# Etapa_Control_Ruido.net
KiCad netlist of a schematic drawn in Altium Designer
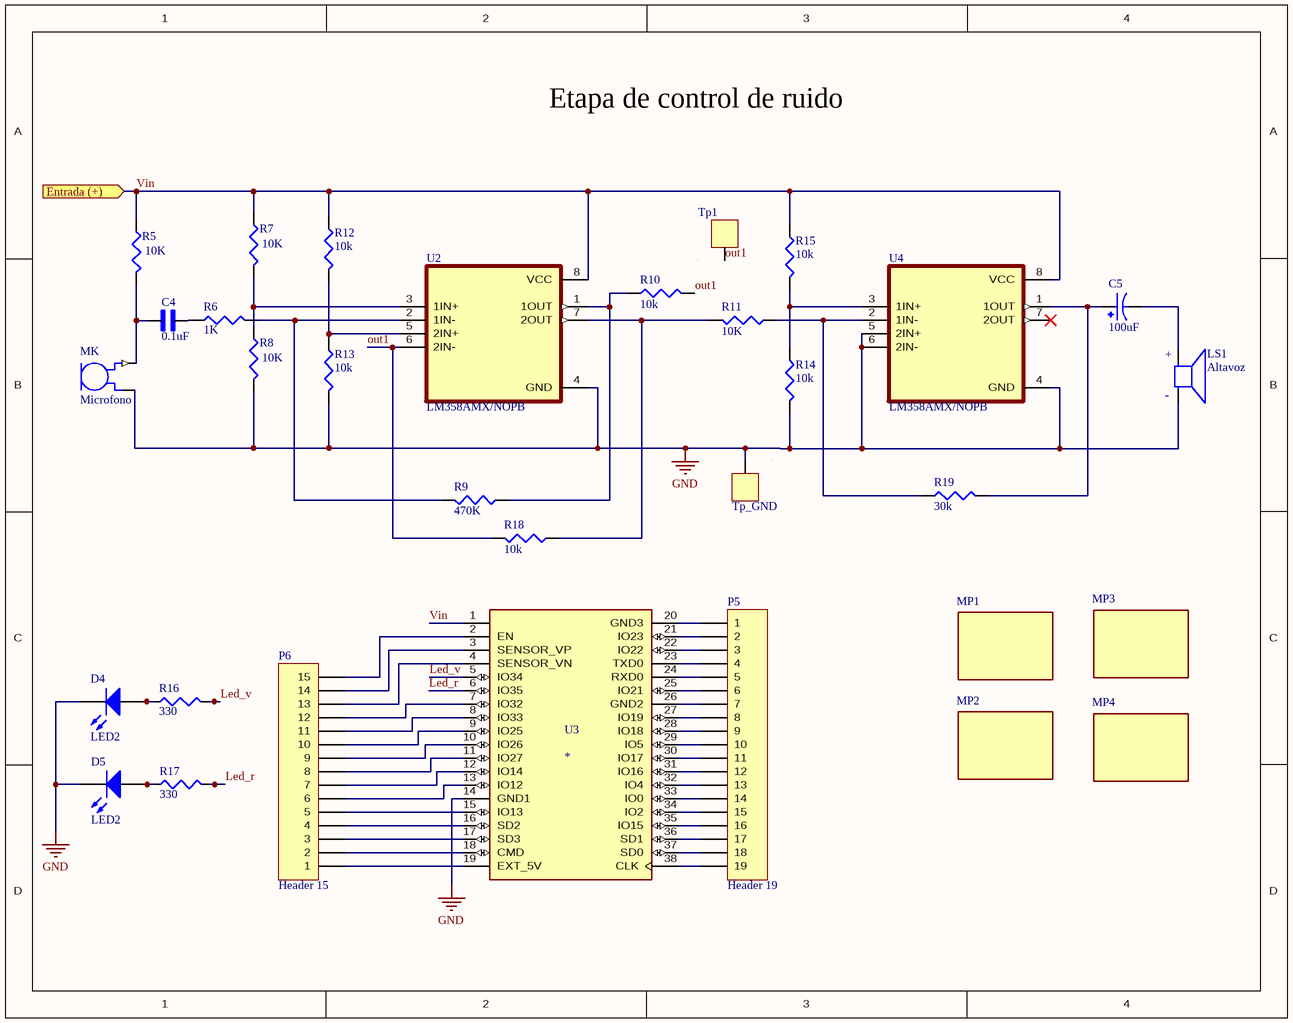
[diagram p0: Etapa_Control_Ruido.schdoc]

(export (version "E")
  (design (tool "Eeschema 10.0.6"))
  (components
    (comp (ref "C4")
      (value "0.1uF")
      (footprint "CAPC4632X221N")
      (fields (field (name "MP") "1812CC104KAZ1A"))
      (libsource (lib "CAP_01uf") (part "1812CC104KAZ1A"))
    )
    (comp (ref "C5")
      (value "100uF")
      (footprint "CAP_16SVPG220M")
      (fields (field (name "MP") "16SVPG220M"))
      (libsource (lib "CAP_220uF") (part "16SVPG220M"))
    )
    (comp (ref "D4")
      (value "LED2")
      (footprint "3.2X1.6X1.1")
      (description "Typical RED, GREEN, YELLOW, AMBER GaAs LED")
      (fields (field (name "PUBLISHER") "Altium Limited"))
      (libsource (lib "Miscellaneous Devices") (part "LED2"))
    )
    (comp (ref "D5")
      (value "LED2")
      (footprint "3.2X1.6X1.1")
      (description "Typical RED, GREEN, YELLOW, AMBER GaAs LED")
      (fields (field (name "PUBLISHER") "Altium Limited"))
      (libsource (lib "Miscellaneous Devices") (part "LED2"))
    )
    (comp (ref "LS1")
      (value "Altavoz")
      (footprint "SPKR_AST-1732MR-R")
      (description "æ‰¬å£°å™¨.2W 32æ¬§å§†90DBA 1700HZ")
      (fields (field (name "MF") "PUI Audio") (field (name "MP") "AST-1732MR-R"))
      (libsource (lib "Altavoz") (part "AST-1732MR-R"))
    )
    (comp (ref "MK")
      (value "Microfono")
      (footprint "CUI_CMA-6542PF")
      (description "9.7 mm, Omnidirectional, PCB Mount, 4.5 Vdc, Electret Condenser Microphone")
      (fields (field (name "MF") "CUI Devices") (field (name "MP") "CMA-6542PF"))
      (libsource (lib "Microfono") (part "CMA-6542PF"))
    )
    (comp (ref "MP1")
      (value "5205980-1")
      (footprint "Tornillo")
      (description "CONN D-SUB SCREW RETAINER MALE")
      (libsource (lib "Altium Content Vault") (part "CMP-03367-000025-1"))
    )
    (comp (ref "MP2")
      (value "5205980-1")
      (footprint "Tornillo")
      (description "CONN D-SUB SCREW RETAINER MALE")
      (libsource (lib "Altium Content Vault") (part "CMP-03367-000025-1"))
    )
    (comp (ref "MP3")
      (value "5205980-1")
      (footprint "Tornillo")
      (description "CONN D-SUB SCREW RETAINER MALE")
      (libsource (lib "Altium Content Vault") (part "CMP-03367-000025-1"))
    )
    (comp (ref "MP4")
      (value "5205980-1")
      (footprint "Tornillo")
      (description "CONN D-SUB SCREW RETAINER MALE")
      (libsource (lib "Altium Content Vault") (part "CMP-03367-000025-1"))
    )
    (comp (ref "P5")
      (value "Header 19")
      (footprint "HDR1X19")
      (description "Header, 19-Pin")
      (fields (field (name "PUBLISHER") "Altium Limited"))
      (libsource (lib "Miscellaneous Connectors") (part "Header 19"))
    )
    (comp (ref "P6")
      (value "Header 15")
      (footprint "HDR1X15")
      (description "Header, 15-Pin")
      (fields (field (name "PUBLISHER") "Altium Limited"))
      (libsource (lib "Miscellaneous Connectors") (part "Header 15"))
    )
    (comp (ref "R5")
      (value "10K")
      (footprint "J1-0805")
      (description "Resistor")
      (fields (field (name "Comment") "Res3") (field (name "PUBLISHER") "Altium Limited"))
      (libsource (lib "Miscellaneous Devices") (part "Res3"))
    )
    (comp (ref "R6")
      (value "1K")
      (footprint "J1-0805")
      (description "Resistor")
      (fields (field (name "Comment") "Res3") (field (name "PUBLISHER") "Altium Limited"))
      (libsource (lib "Miscellaneous Devices") (part "Res3"))
    )
    (comp (ref "R7")
      (value "10K")
      (footprint "J1-0805")
      (description "Resistor")
      (fields (field (name "Comment") "Res3") (field (name "PUBLISHER") "Altium Limited"))
      (libsource (lib "Miscellaneous Devices") (part "Res3"))
    )
    (comp (ref "R8")
      (value "10K")
      (footprint "J1-0805")
      (description "Resistor")
      (fields (field (name "Comment") "Res3") (field (name "PUBLISHER") "Altium Limited"))
      (libsource (lib "Miscellaneous Devices") (part "Res3"))
    )
    (comp (ref "R9")
      (value "470K")
      (footprint "J1-1206")
      (description "Resistor")
      (fields (field (name "Comment") "Res3") (field (name "PUBLISHER") "Altium Limited"))
      (libsource (lib "Miscellaneous Devices") (part "Res3"))
    )
    (comp (ref "R10")
      (value "10k")
      (footprint "J1-0805")
      (description "Resistor")
      (fields (field (name "Comment") "Res3") (field (name "PUBLISHER") "Altium Limited"))
      (libsource (lib "Miscellaneous Devices") (part "Res3"))
    )
    (comp (ref "R11")
      (value "10K")
      (footprint "J1-0805")
      (description "Resistor")
      (fields (field (name "Comment") "Res3") (field (name "PUBLISHER") "Altium Limited"))
      (libsource (lib "Miscellaneous Devices") (part "Res3"))
    )
    (comp (ref "R12")
      (value "10k")
      (footprint "J1-0805")
      (description "Resistor")
      (fields (field (name "Comment") "Res3") (field (name "PUBLISHER") "Altium Limited"))
      (libsource (lib "Miscellaneous Devices") (part "Res3"))
    )
    (comp (ref "R13")
      (value "10k")
      (footprint "J1-0805")
      (description "Resistor")
      (fields (field (name "Comment") "Res3") (field (name "PUBLISHER") "Altium Limited"))
      (libsource (lib "Miscellaneous Devices") (part "Res3"))
    )
    (comp (ref "R14")
      (value "10k")
      (footprint "J1-0805")
      (description "Resistor")
      (fields (field (name "Comment") "Res3") (field (name "PUBLISHER") "Altium Limited"))
      (libsource (lib "Miscellaneous Devices") (part "Res3"))
    )
    (comp (ref "R15")
      (value "10k")
      (footprint "J1-0805")
      (description "Resistor")
      (fields (field (name "Comment") "Res3") (field (name "PUBLISHER") "Altium Limited"))
      (libsource (lib "Miscellaneous Devices") (part "Res3"))
    )
    (comp (ref "R16")
      (value "330")
      (footprint "J1-0805")
      (description "Resistor")
      (fields (field (name "Comment") "Res3") (field (name "PUBLISHER") "Altium Limited"))
      (libsource (lib "Miscellaneous Devices") (part "Res3"))
    )
    (comp (ref "R17")
      (value "330")
      (footprint "J1-0805")
      (description "Resistor")
      (fields (field (name "Comment") "Res3") (field (name "PUBLISHER") "Altium Limited"))
      (libsource (lib "Miscellaneous Devices") (part "Res3"))
    )
    (comp (ref "R18")
      (value "10k")
      (footprint "J1-0805")
      (description "Resistor")
      (fields (field (name "Comment") "Res3") (field (name "PUBLISHER") "Altium Limited"))
      (libsource (lib "Miscellaneous Devices") (part "Res3"))
    )
    (comp (ref "R19")
      (value "30k")
      (footprint "J1-0805")
      (description "Resistor")
      (fields (field (name "Comment") "Res3") (field (name "PUBLISHER") "Altium Limited"))
      (libsource (lib "Miscellaneous Devices") (part "Res3"))
    )
    (comp (ref "Tp1")
      (value "Test_point")
      (footprint "Test_Point")
      (libsource (lib "") (part "Test_point_1"))
    )
    (comp (ref "Tp_GND")
      (value "Test_point")
      (footprint "Test_point_GND")
      (libsource (lib "Test_point") (part "Test_point"))
    )
    (comp (ref "U2")
      (value "LM358AMX/NOPB")
      (footprint "SOIC127P599X175-8N")
      (description "2-Channel, 1MHz, industry standard, 32V op amp 8-SOIC 0 to 70")
      (fields (field (name "MF") "Texas Instruments"))
      (libsource (lib "Lm358") (part "LM358AMX/NOPB"))
    )
    (comp (ref "U3")
      (value "*")
      (footprint "MODULE_ESP32-DEVKITC-32D")
      (description "EVAL BOARD FOR ESP-WROOM-32")
      (fields (field (name "MP") "ESP32-DEVKITC-32D") (field (name "MF") "Espressif Systems"))
      (libsource (lib "*") (part "ESP32-DEVKITC-32D"))
    )
    (comp (ref "U4")
      (value "LM358AMX/NOPB")
      (footprint "SOIC127P599X175-8N")
      (description "2-Channel, 1MHz, industry standard, 32V op amp 8-SOIC 0 to 70")
      (fields (field (name "MF") "Texas Instruments"))
      (libsource (lib "Lm358") (part "LM358AMX/NOPB"))
    )
  )
  (nets
    (net (code "1") (name "/Led_r") (class "Default")
      (node (ref "R17") (pin "2") (pinfunction "2_2") (pintype "passive"))
      (node (ref "U3") (pin "6") (pinfunction "IO35_6") (pintype "bidirectional"))
    )
    (net (code "2") (name "/Led_v") (class "Default")
      (node (ref "R16") (pin "2") (pinfunction "2_2") (pintype "passive"))
      (node (ref "U3") (pin "5") (pinfunction "IO34_5") (pintype "bidirectional"))
    )
    (net (code "3") (name "/Vin") (class "Default")
      (node (ref "R12") (pin "1") (pinfunction "1_1") (pintype "passive"))
      (node (ref "R15") (pin "1") (pinfunction "1_1") (pintype "passive"))
      (node (ref "R5") (pin "1") (pinfunction "1_1") (pintype "passive"))
      (node (ref "R7") (pin "1") (pinfunction "1_1") (pintype "passive"))
      (node (ref "U2") (pin "8") (pinfunction "VCC_8") (pintype "passive"))
      (node (ref "U3") (pin "1") (pinfunction "3V3_1") (pintype "passive"))
      (node (ref "U4") (pin "8") (pinfunction "VCC_8") (pintype "passive"))
    )
    (net (code "4") (name "/out1") (class "Default")
      (node (ref "R10") (pin "2") (pinfunction "2_2") (pintype "passive"))
      (node (ref "R18") (pin "2") (pinfunction "2_2") (pintype "passive"))
      (node (ref "Tp1") (pin "1") (pinfunction "1_1") (pintype "passive"))
      (node (ref "U2") (pin "6") (pinfunction "2IN-_6") (pintype "passive"))
    )
    (net (code "5") (name "GND") (class "Default")
      (node (ref "D4") (pin "2") (pinfunction "K_2") (pintype "passive"))
      (node (ref "D5") (pin "2") (pinfunction "K_2") (pintype "passive"))
      (node (ref "LS1") (pin "2") (pinfunction "NEG_2") (pintype "passive"))
      (node (ref "MK") (pin "2") (pinfunction "2_2") (pintype "power_in"))
      (node (ref "R13") (pin "2") (pinfunction "2_2") (pintype "passive"))
      (node (ref "R14") (pin "2") (pinfunction "2_2") (pintype "passive"))
      (node (ref "R8") (pin "2") (pinfunction "2_2") (pintype "passive"))
      (node (ref "Tp_GND") (pin "1") (pinfunction "1_1") (pintype "passive"))
      (node (ref "U2") (pin "4") (pinfunction "GND_4") (pintype "power_in"))
      (node (ref "U3") (pin "14") (pinfunction "GND1_14") (pintype "power_in"))
      (node (ref "U4") (pin "4") (pinfunction "GND_4") (pintype "power_in"))
      (node (ref "U4") (pin "5") (pinfunction "2IN+_5") (pintype "passive"))
      (node (ref "U4") (pin "6") (pinfunction "2IN-_6") (pintype "passive"))
    )
    (net (code "6") (name "Net-(C4-Pad1)") (class "Default")
      (node (ref "C4") (pin "1") (pinfunction "1_1") (pintype "passive"))
      (node (ref "R6") (pin "1") (pinfunction "1_1") (pintype "passive"))
    )
    (net (code "7") (name "Net-(D4-A)") (class "Default")
      (node (ref "D4") (pin "1") (pinfunction "A_1") (pintype "passive"))
      (node (ref "R16") (pin "1") (pinfunction "1_1") (pintype "passive"))
    )
    (net (code "8") (name "Net-(D5-A)") (class "Default")
      (node (ref "D5") (pin "1") (pinfunction "A_1") (pintype "passive"))
      (node (ref "R17") (pin "1") (pinfunction "1_1") (pintype "passive"))
    )
    (net (code "9") (name "Net-(LS1-POS)") (class "Default")
      (node (ref "C5") (pin "2") (pinfunction "2_2") (pintype "passive"))
      (node (ref "LS1") (pin "1") (pinfunction "POS_1") (pintype "passive"))
    )
    (net (code "10") (name "Net-(MK-OUT)") (class "Default")
      (node (ref "C4") (pin "2") (pinfunction "2_2") (pintype "passive"))
      (node (ref "MK") (pin "1") (pinfunction "OUT_1") (pintype "output"))
      (node (ref "R5") (pin "2") (pinfunction "2_2") (pintype "passive"))
    )
    (net (code "11") (name "Net-(U2-1IN+)") (class "Default")
      (node (ref "R7") (pin "2") (pinfunction "2_2") (pintype "passive"))
      (node (ref "R8") (pin "1") (pinfunction "1_1") (pintype "passive"))
      (node (ref "U2") (pin "3") (pinfunction "1IN+_3") (pintype "passive"))
    )
    (net (code "12") (name "Net-(U2-1IN-)") (class "Default")
      (node (ref "R6") (pin "2") (pinfunction "2_2") (pintype "passive"))
      (node (ref "R9") (pin "2") (pinfunction "2_2") (pintype "passive"))
      (node (ref "U2") (pin "2") (pinfunction "1IN-_2") (pintype "passive"))
    )
    (net (code "13") (name "Net-(U2-1OUT)") (class "Default")
      (node (ref "R10") (pin "1") (pinfunction "1_1") (pintype "passive"))
      (node (ref "R9") (pin "1") (pinfunction "1_1") (pintype "passive"))
      (node (ref "U2") (pin "1") (pinfunction "1OUT_1") (pintype "output"))
    )
    (net (code "14") (name "Net-(U2-2IN+)") (class "Default")
      (node (ref "R12") (pin "2") (pinfunction "2_2") (pintype "passive"))
      (node (ref "R13") (pin "1") (pinfunction "1_1") (pintype "passive"))
      (node (ref "U2") (pin "5") (pinfunction "2IN+_5") (pintype "passive"))
    )
    (net (code "15") (name "Net-(U2-2OUT)") (class "Default")
      (node (ref "R11") (pin "2") (pinfunction "2_2") (pintype "passive"))
      (node (ref "R18") (pin "1") (pinfunction "1_1") (pintype "passive"))
      (node (ref "U2") (pin "7") (pinfunction "2OUT_7") (pintype "output"))
    )
    (net (code "16") (name "Net-(U3-CLK)") (class "Default")
      (node (ref "P5") (pin "19") (pinfunction "19_19") (pintype "passive"))
      (node (ref "U3") (pin "38") (pinfunction "CLK_38") (pintype "passive"))
    )
    (net (code "17") (name "Net-(U3-CMD)") (class "Default")
      (node (ref "P6") (pin "2") (pinfunction "2_2") (pintype "passive"))
      (node (ref "U3") (pin "18") (pinfunction "CMD_18") (pintype "bidirectional"))
    )
    (net (code "18") (name "Net-(U3-EN)") (class "Default")
      (node (ref "P6") (pin "15") (pinfunction "15_15") (pintype "passive"))
      (node (ref "U3") (pin "2") (pinfunction "EN_2") (pintype "passive"))
    )
    (net (code "19") (name "Net-(U3-EXT_5V)") (class "Default")
      (node (ref "P6") (pin "1") (pinfunction "1_1") (pintype "passive"))
      (node (ref "U3") (pin "19") (pinfunction "EXT_5V_19") (pintype "power_in"))
    )
    (net (code "20") (name "Net-(U3-GND2)") (class "Default")
      (node (ref "P5") (pin "7") (pinfunction "7_7") (pintype "passive"))
      (node (ref "U3") (pin "26") (pinfunction "GND2_26") (pintype "power_in"))
    )
    (net (code "21") (name "Net-(U3-GND3)") (class "Default")
      (node (ref "P5") (pin "1") (pinfunction "1_1") (pintype "passive"))
      (node (ref "U3") (pin "20") (pinfunction "GND3_20") (pintype "power_in"))
    )
    (net (code "22") (name "Net-(U3-IO0)") (class "Default")
      (node (ref "P5") (pin "14") (pinfunction "14_14") (pintype "passive"))
      (node (ref "U3") (pin "33") (pinfunction "IO0_33") (pintype "bidirectional"))
    )
    (net (code "23") (name "Net-(U3-IO2)") (class "Default")
      (node (ref "P5") (pin "15") (pinfunction "15_15") (pintype "passive"))
      (node (ref "U3") (pin "34") (pinfunction "IO2_34") (pintype "bidirectional"))
    )
    (net (code "24") (name "Net-(U3-IO4)") (class "Default")
      (node (ref "P5") (pin "13") (pinfunction "13_13") (pintype "passive"))
      (node (ref "U3") (pin "32") (pinfunction "IO4_32") (pintype "bidirectional"))
    )
    (net (code "25") (name "Net-(U3-IO5)") (class "Default")
      (node (ref "P5") (pin "10") (pinfunction "10_10") (pintype "passive"))
      (node (ref "U3") (pin "29") (pinfunction "IO5_29") (pintype "bidirectional"))
    )
    (net (code "26") (name "Net-(U3-IO12)") (class "Default")
      (node (ref "P6") (pin "6") (pinfunction "6_6") (pintype "passive"))
      (node (ref "U3") (pin "13") (pinfunction "IO12_13") (pintype "bidirectional"))
    )
    (net (code "27") (name "Net-(U3-IO13)") (class "Default")
      (node (ref "P6") (pin "5") (pinfunction "5_5") (pintype "passive"))
      (node (ref "U3") (pin "15") (pinfunction "IO13_15") (pintype "bidirectional"))
    )
    (net (code "28") (name "Net-(U3-IO14)") (class "Default")
      (node (ref "P6") (pin "7") (pinfunction "7_7") (pintype "passive"))
      (node (ref "U3") (pin "12") (pinfunction "IO14_12") (pintype "bidirectional"))
    )
    (net (code "29") (name "Net-(U3-IO15)") (class "Default")
      (node (ref "P5") (pin "16") (pinfunction "16_16") (pintype "passive"))
      (node (ref "U3") (pin "35") (pinfunction "IO15_35") (pintype "bidirectional"))
    )
    (net (code "30") (name "Net-(U3-IO16)") (class "Default")
      (node (ref "P5") (pin "12") (pinfunction "12_12") (pintype "passive"))
      (node (ref "U3") (pin "31") (pinfunction "IO16_31") (pintype "bidirectional"))
    )
    (net (code "31") (name "Net-(U3-IO17)") (class "Default")
      (node (ref "P5") (pin "11") (pinfunction "11_11") (pintype "passive"))
      (node (ref "U3") (pin "30") (pinfunction "IO17_30") (pintype "bidirectional"))
    )
    (net (code "32") (name "Net-(U3-IO18)") (class "Default")
      (node (ref "P5") (pin "9") (pinfunction "9_9") (pintype "passive"))
      (node (ref "U3") (pin "28") (pinfunction "IO18_28") (pintype "bidirectional"))
    )
    (net (code "33") (name "Net-(U3-IO19)") (class "Default")
      (node (ref "P5") (pin "8") (pinfunction "8_8") (pintype "passive"))
      (node (ref "U3") (pin "27") (pinfunction "IO19_27") (pintype "bidirectional"))
    )
    (net (code "34") (name "Net-(U3-IO21)") (class "Default")
      (node (ref "P5") (pin "6") (pinfunction "6_6") (pintype "passive"))
      (node (ref "U3") (pin "25") (pinfunction "IO21_25") (pintype "bidirectional"))
    )
    (net (code "35") (name "Net-(U3-IO22)") (class "Default")
      (node (ref "P5") (pin "3") (pinfunction "3_3") (pintype "passive"))
      (node (ref "U3") (pin "22") (pinfunction "IO22_22") (pintype "bidirectional"))
    )
    (net (code "36") (name "Net-(U3-IO23)") (class "Default")
      (node (ref "P5") (pin "2") (pinfunction "2_2") (pintype "passive"))
      (node (ref "U3") (pin "21") (pinfunction "IO23_21") (pintype "bidirectional"))
    )
    (net (code "37") (name "Net-(U3-IO25)") (class "Default")
      (node (ref "P6") (pin "10") (pinfunction "10_10") (pintype "passive"))
      (node (ref "U3") (pin "9") (pinfunction "IO25_9") (pintype "bidirectional"))
    )
    (net (code "38") (name "Net-(U3-IO26)") (class "Default")
      (node (ref "P6") (pin "9") (pinfunction "9_9") (pintype "passive"))
      (node (ref "U3") (pin "10") (pinfunction "IO26_10") (pintype "bidirectional"))
    )
    (net (code "39") (name "Net-(U3-IO27)") (class "Default")
      (node (ref "P6") (pin "8") (pinfunction "8_8") (pintype "passive"))
      (node (ref "U3") (pin "11") (pinfunction "IO27_11") (pintype "bidirectional"))
    )
    (net (code "40") (name "Net-(U3-IO32)") (class "Default")
      (node (ref "P6") (pin "12") (pinfunction "12_12") (pintype "passive"))
      (node (ref "U3") (pin "7") (pinfunction "IO32_7") (pintype "bidirectional"))
    )
    (net (code "41") (name "Net-(U3-IO33)") (class "Default")
      (node (ref "P6") (pin "11") (pinfunction "11_11") (pintype "passive"))
      (node (ref "U3") (pin "8") (pinfunction "IO33_8") (pintype "bidirectional"))
    )
    (net (code "42") (name "Net-(U3-RXD0)") (class "Default")
      (node (ref "P5") (pin "5") (pinfunction "5_5") (pintype "passive"))
      (node (ref "U3") (pin "24") (pinfunction "RXD0_24") (pintype "passive"))
    )
    (net (code "43") (name "Net-(U3-SD0)") (class "Default")
      (node (ref "P5") (pin "18") (pinfunction "18_18") (pintype "passive"))
      (node (ref "U3") (pin "37") (pinfunction "SD0_37") (pintype "bidirectional"))
    )
    (net (code "44") (name "Net-(U3-SD1)") (class "Default")
      (node (ref "P5") (pin "17") (pinfunction "17_17") (pintype "passive"))
      (node (ref "U3") (pin "36") (pinfunction "SD1_36") (pintype "bidirectional"))
    )
    (net (code "45") (name "Net-(U3-SD2)") (class "Default")
      (node (ref "P6") (pin "4") (pinfunction "4_4") (pintype "passive"))
      (node (ref "U3") (pin "16") (pinfunction "SD2_16") (pintype "bidirectional"))
    )
    (net (code "46") (name "Net-(U3-SD3)") (class "Default")
      (node (ref "P6") (pin "3") (pinfunction "3_3") (pintype "passive"))
      (node (ref "U3") (pin "17") (pinfunction "SD3_17") (pintype "bidirectional"))
    )
    (net (code "47") (name "Net-(U3-SENSOR_VN)") (class "Default")
      (node (ref "P6") (pin "13") (pinfunction "13_13") (pintype "passive"))
      (node (ref "U3") (pin "4") (pinfunction "SENSOR_VN_4") (pintype "passive"))
    )
    (net (code "48") (name "Net-(U3-SENSOR_VP)") (class "Default")
      (node (ref "P6") (pin "14") (pinfunction "14_14") (pintype "passive"))
      (node (ref "U3") (pin "3") (pinfunction "SENSOR_VP_3") (pintype "passive"))
    )
    (net (code "49") (name "Net-(U3-TXD0)") (class "Default")
      (node (ref "P5") (pin "4") (pinfunction "4_4") (pintype "passive"))
      (node (ref "U3") (pin "23") (pinfunction "TXD0_23") (pintype "passive"))
    )
    (net (code "50") (name "Net-(U4-1IN+)") (class "Default")
      (node (ref "R14") (pin "1") (pinfunction "1_1") (pintype "passive"))
      (node (ref "R15") (pin "2") (pinfunction "2_2") (pintype "passive"))
      (node (ref "U4") (pin "3") (pinfunction "1IN+_3") (pintype "passive"))
    )
    (net (code "51") (name "Net-(U4-1IN-)") (class "Default")
      (node (ref "R11") (pin "1") (pinfunction "1_1") (pintype "passive"))
      (node (ref "R19") (pin "1") (pinfunction "1_1") (pintype "passive"))
      (node (ref "U4") (pin "2") (pinfunction "1IN-_2") (pintype "passive"))
    )
    (net (code "52") (name "Net-(U4-1OUT)") (class "Default")
      (node (ref "C5") (pin "1") (pinfunction "1_1") (pintype "passive"))
      (node (ref "R19") (pin "2") (pinfunction "2_2") (pintype "passive"))
      (node (ref "U4") (pin "1") (pinfunction "1OUT_1") (pintype "output"))
    )
    (net (code "53") (name "unconnected-(U4-2OUT-Pad7)") (class "Default")
      (node (ref "U4") (pin "7") (pinfunction "2OUT_7") (pintype "output+no_connect"))
    )
  )
)
